# DUE_Xbee_v1.net
KiCad netlist of a schematic drawn in EAGLE
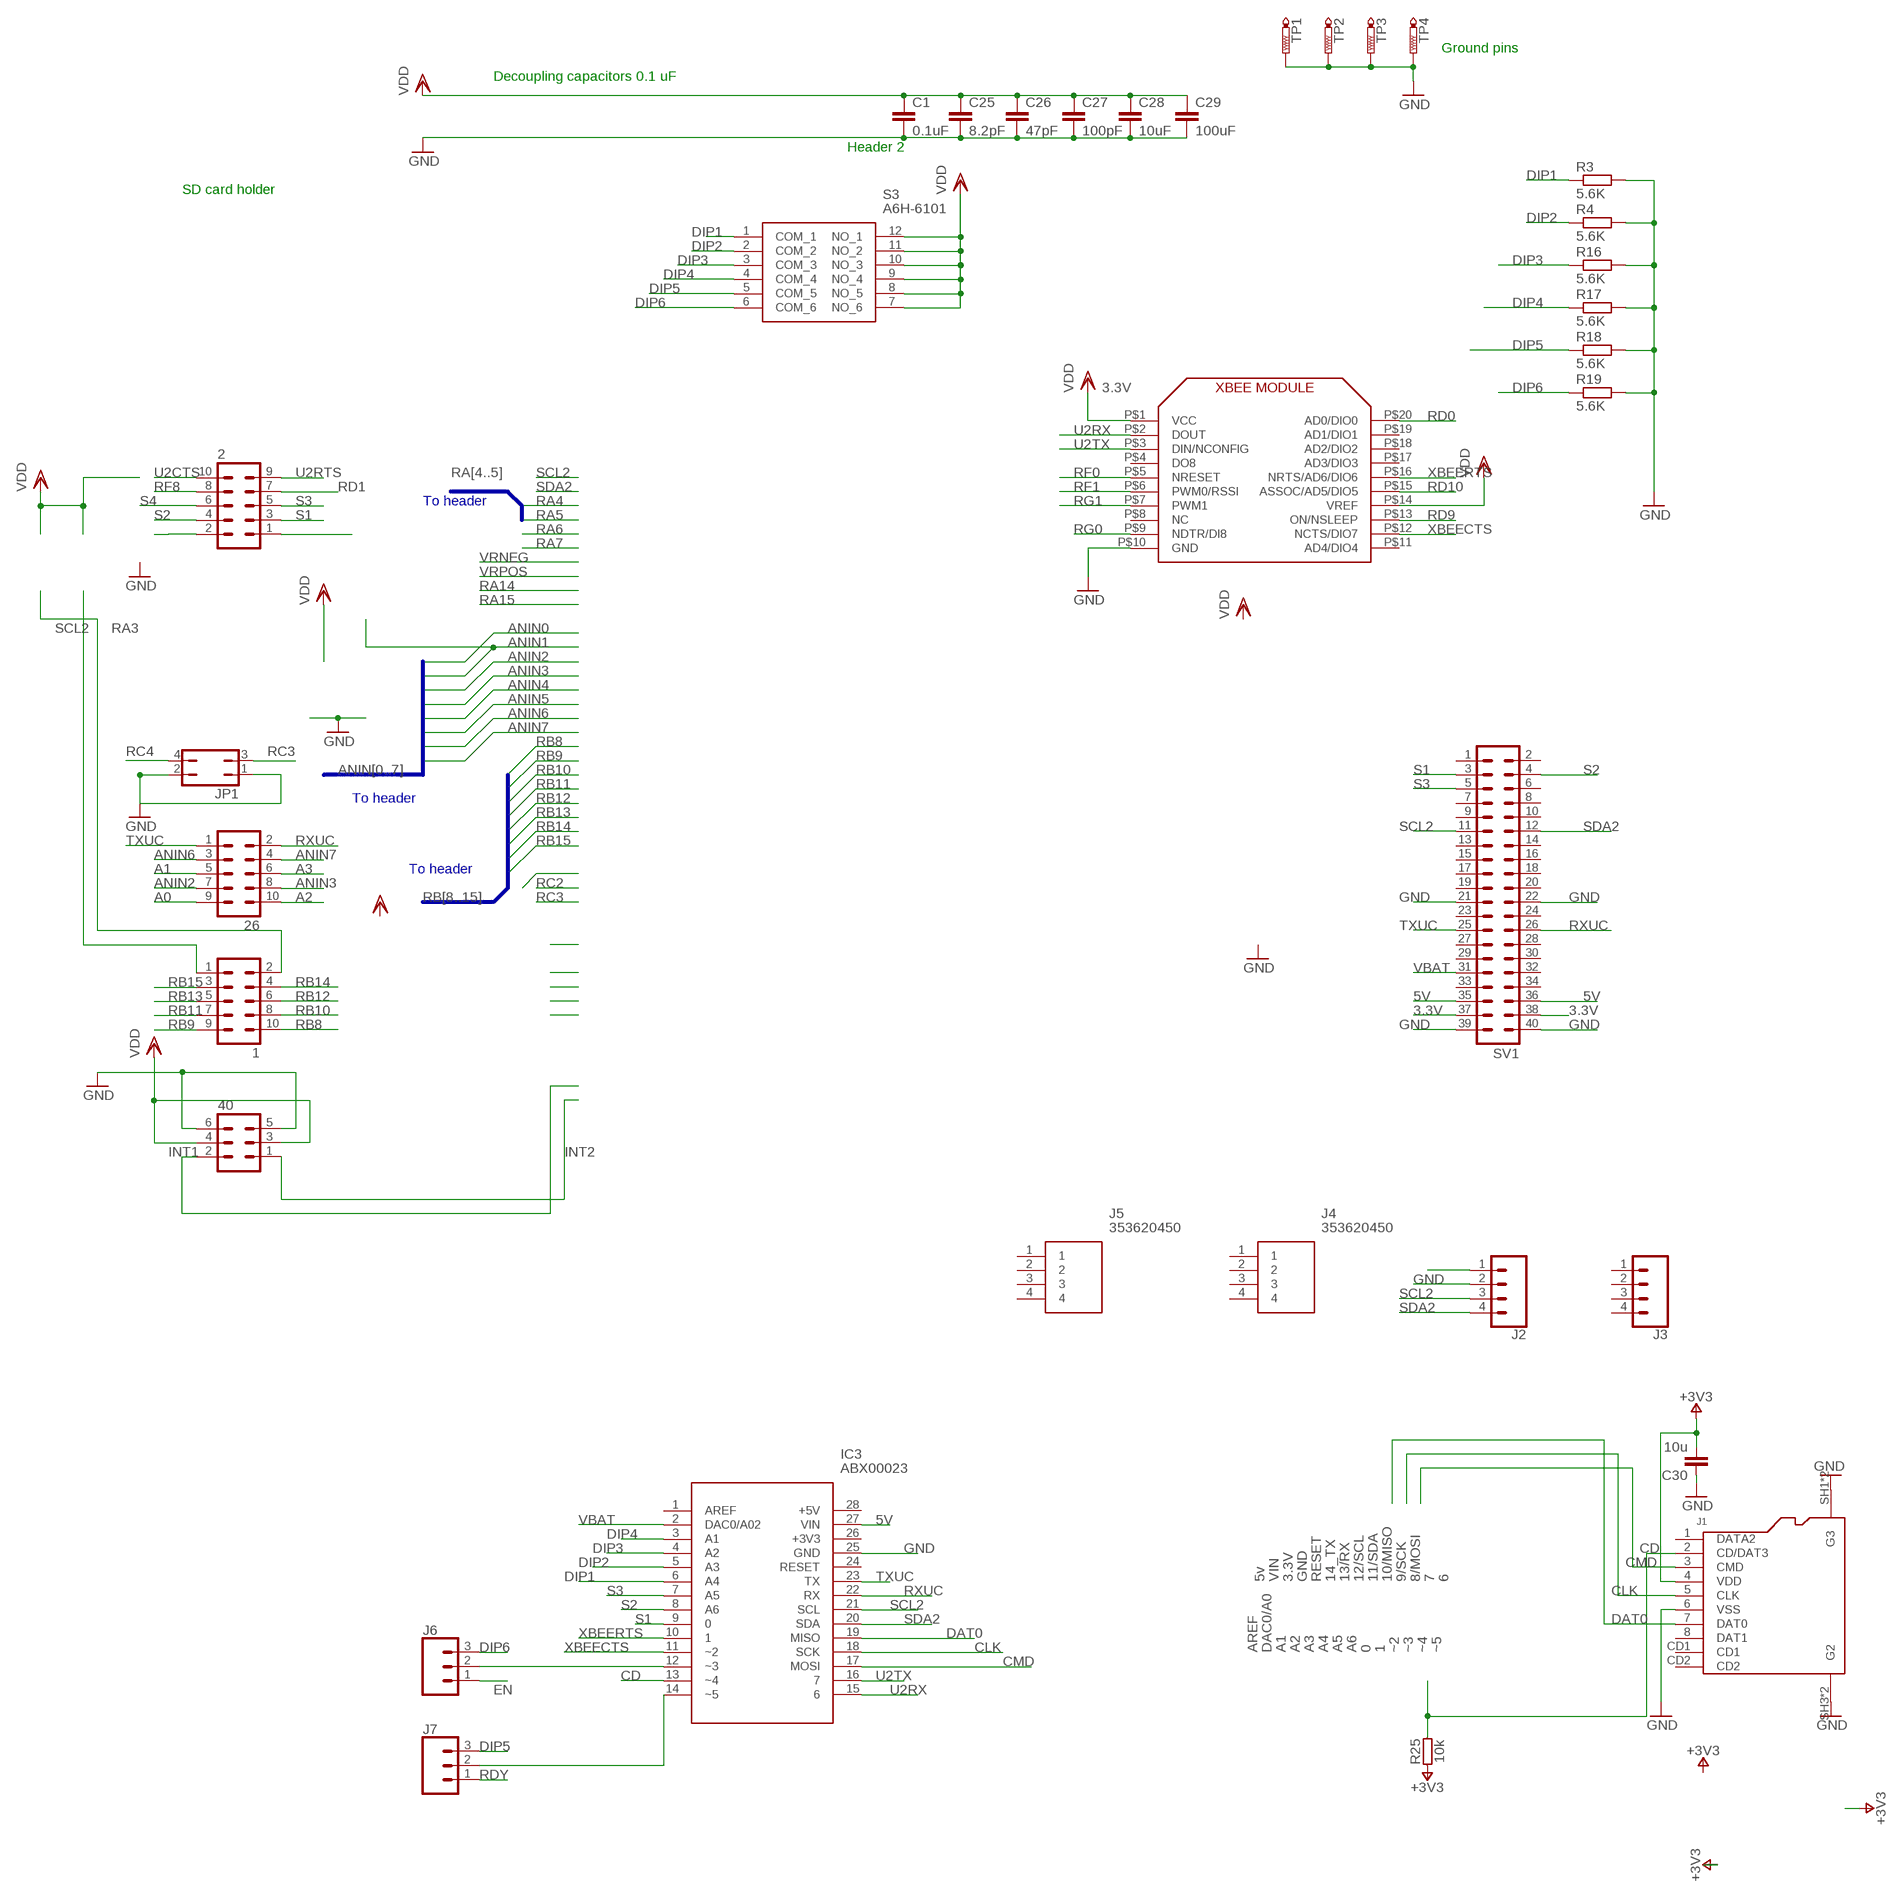
[diagram p0: schematic, sheet 1, part 1 of 2]
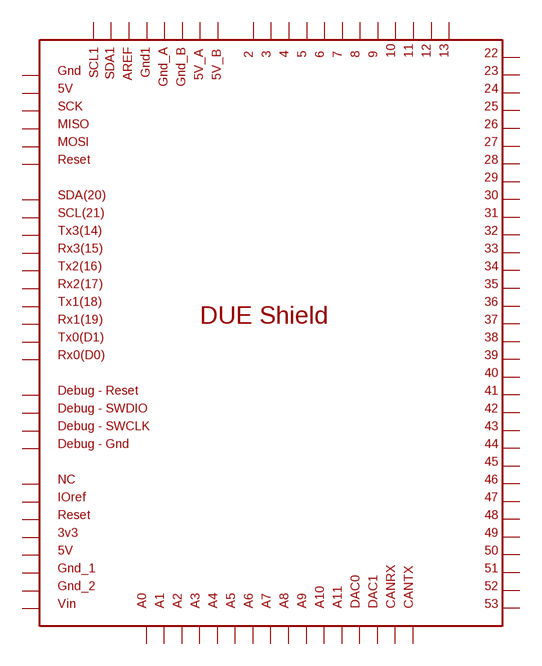
[diagram p1: schematic, sheet 1, part 2 of 2]

(export (version "E")
  (design (tool "Eeschema 10.0.6"))
  (components
    (comp (ref "1")
      (value "MA05-2")
      (footprint "eagle-import:MA05-2")
      (libsource (lib "eagle-import") (part "MA05-2"))
    )
    (comp (ref "2")
      (value "MA05-2")
      (footprint "eagle-import:MA05-2")
      (libsource (lib "eagle-import") (part "MA05-2"))
    )
    (comp (ref "26")
      (value "MA05-2")
      (footprint "eagle-import:MA05-2")
      (libsource (lib "eagle-import") (part "MA05-2"))
    )
    (comp (ref "40")
      (value "MA03-2")
      (footprint "eagle-import:MA03-2")
      (libsource (lib "eagle-import") (part "MA03-2"))
    )
    (comp (ref "C1")
      (value "0.1uF")
      (footprint "eagle-import:C0805K")
      (libsource (lib "eagle-import") (part "C-EUC0805K"))
    )
    (comp (ref "C25")
      (value "8.2pF")
      (footprint "eagle-import:C0805K")
      (libsource (lib "eagle-import") (part "C-EUC0805K"))
    )
    (comp (ref "C26")
      (value "47pF")
      (footprint "eagle-import:C0805K")
      (libsource (lib "eagle-import") (part "C-EUC0805K"))
    )
    (comp (ref "C27")
      (value "100pF")
      (footprint "eagle-import:C0805K")
      (libsource (lib "eagle-import") (part "C-EUC0805K"))
    )
    (comp (ref "C28")
      (value "10uF")
      (footprint "eagle-import:C0805K")
      (libsource (lib "eagle-import") (part "C-EUC0805K"))
    )
    (comp (ref "C29")
      (value "100uF")
      (footprint "eagle-import:C0805K")
      (libsource (lib "eagle-import") (part "C-EUC0805K"))
    )
    (comp (ref "C30")
      (value "10u")
      (footprint "eagle-import:0805-R2013X50N")
      (fields (field (name "MANUFACTURER") "Samsung"))
      (libsource (lib "eagle-import") (part "C-0805-22U"))
    )
    (comp (ref "IC3")
      (value "ABX00023")
      (footprint "eagle-import:ABX00023")
      (fields (field (name "MOUSER_PART_NUMBER") "782-ABX00023"))
      (libsource (lib "eagle-import") (part "ABX00023"))
    )
    (comp (ref "J1")
      (value "AMPHENOL_114-00841-68")
      (footprint "eagle-import:AMPHENOL_114-00841-68")
      (libsource (lib "eagle-import") (part "AMPHENOL_114-00841-68"))
    )
    (comp (ref "J2")
      (value "CONN_04POLAR_LOCK")
      (footprint "eagle-import:MOLEX-1X4_LOCK")
      (libsource (lib "eagle-import") (part "CONN_04POLAR_LOCK"))
    )
    (comp (ref "J3")
      (value "CONN_04POLAR_LOCK")
      (footprint "eagle-import:MOLEX-1X4_LOCK")
      (libsource (lib "eagle-import") (part "CONN_04POLAR_LOCK"))
    )
    (comp (ref "J4")
      (value "353620450")
      (footprint "eagle-import:SHDR4W50P0X200_1X4_1030X550X85")
      (libsource (lib "eagle-import") (part "353620450"))
    )
    (comp (ref "J5")
      (value "353620450")
      (footprint "eagle-import:SHDR4W50P0X200_1X4_1030X550X85")
      (libsource (lib "eagle-import") (part "353620450"))
    )
    (comp (ref "J6")
      (value "CONN_03LOCK")
      (footprint "eagle-import:1X03_LOCK")
      (libsource (lib "eagle-import") (part "CONN_03LOCK"))
    )
    (comp (ref "J7")
      (value "CONN_03LOCK")
      (footprint "eagle-import:1X03_LOCK")
      (libsource (lib "eagle-import") (part "CONN_03LOCK"))
    )
    (comp (ref "JP1")
      (value "JP2Q")
      (footprint "eagle-import:JP2Q")
      (libsource (lib "eagle-import") (part "JP2Q"))
    )
    (comp (ref "R3")
      (value "5.6K")
      (footprint "eagle-import:R0805")
      (libsource (lib "eagle-import") (part "R-EU_R0805"))
    )
    (comp (ref "R4")
      (value "5.6K")
      (footprint "eagle-import:R0805")
      (libsource (lib "eagle-import") (part "R-EU_R0805"))
    )
    (comp (ref "R16")
      (value "5.6K")
      (footprint "eagle-import:R0805")
      (libsource (lib "eagle-import") (part "R-EU_R0805"))
    )
    (comp (ref "R17")
      (value "5.6K")
      (footprint "eagle-import:R0805")
      (libsource (lib "eagle-import") (part "R-EU_R0805"))
    )
    (comp (ref "R18")
      (value "5.6K")
      (footprint "eagle-import:R0805")
      (libsource (lib "eagle-import") (part "R-EU_R0805"))
    )
    (comp (ref "R19")
      (value "5.6K")
      (footprint "eagle-import:R0805")
      (libsource (lib "eagle-import") (part "R-EU_R0805"))
    )
    (comp (ref "R25")
      (value "10k")
      (footprint "eagle-import:0805-R2013X50N")
      (fields (field (name "MANUFACTURER") "DNP"))
      (libsource (lib "eagle-import") (part "R-0805-DNP"))
    )
    (comp (ref "S3")
      (value "A6H-6101")
      (footprint "eagle-import:A6H6101")
      (fields (field (name "MOUSER_PART_NUMBER") "653-A6H-6101"))
      (libsource (lib "eagle-import") (part "A6H-6101"))
    )
    (comp (ref "SV1")
      (value "ML40")
      (footprint "eagle-import:ML40")
      (libsource (lib "eagle-import") (part "ML40"))
    )
    (comp (ref "TP1")
      (value "PTR1PAD1-13")
      (footprint "eagle-import:P1-13")
      (libsource (lib "eagle-import") (part "PTR1PAD1-13"))
    )
    (comp (ref "TP2")
      (value "PTR1PAD1-13")
      (footprint "eagle-import:P1-13")
      (libsource (lib "eagle-import") (part "PTR1PAD1-13"))
    )
    (comp (ref "TP3")
      (value "PTR1PAD1-13")
      (footprint "eagle-import:P1-13")
      (libsource (lib "eagle-import") (part "PTR1PAD1-13"))
    )
    (comp (ref "TP4")
      (value "PTR1PAD1-13")
      (footprint "eagle-import:P1-13")
      (libsource (lib "eagle-import") (part "PTR1PAD1-13"))
    )
    (comp (ref "U$1")
      (value "XBEE")
      (footprint "eagle-import:XBEE")
      (libsource (lib "eagle-import") (part "XBEE"))
    )
    (comp (ref "U$2")
      (value "DUE(NORMAL)")
      (footprint "eagle-import:DUE(NORMAL)")
      (libsource (lib "eagle-import") (part "DUE(NORMAL)"))
    )
  )
  (nets
    (net (code "1") (name "+3V3") (class "Default")
      (node (ref "C30") (pin "2") (pinfunction "2_2") (pintype "passive"))
      (node (ref "J1") (pin "4") (pinfunction "VDD_4") (pintype "power_in"))
      (node (ref "R25") (pin "1") (pinfunction "1_1") (pintype "passive"))
    )
    (net (code "2") (name "/5V") (class "Default")
      (node (ref "IC3") (pin "27") (pinfunction "VIN_27") (pintype "bidirectional"))
      (node (ref "SV1") (pin "35") (pinfunction "35_35") (pintype "passive"))
      (node (ref "SV1") (pin "36") (pinfunction "36_36") (pintype "passive"))
    )
    (net (code "3") (name "/A0") (class "Default")
      (node (ref "26") (pin "9") (pinfunction "9_9") (pintype "passive"))
    )
    (net (code "4") (name "/A1") (class "Default")
      (node (ref "26") (pin "5") (pinfunction "5_5") (pintype "passive"))
    )
    (net (code "5") (name "/A2") (class "Default")
      (node (ref "26") (pin "10") (pinfunction "10_10") (pintype "passive"))
    )
    (net (code "6") (name "/A3") (class "Default")
      (node (ref "26") (pin "6") (pinfunction "6_6") (pintype "passive"))
    )
    (net (code "9") (name "/ANIN2") (class "Default")
      (node (ref "26") (pin "7") (pinfunction "7_7") (pintype "passive"))
    )
    (net (code "10") (name "/ANIN3") (class "Default")
      (node (ref "26") (pin "8") (pinfunction "8_8") (pintype "passive"))
    )
    (net (code "13") (name "/ANIN6") (class "Default")
      (node (ref "26") (pin "3") (pinfunction "3_3") (pintype "passive"))
    )
    (net (code "14") (name "/ANIN7") (class "Default")
      (node (ref "26") (pin "4") (pinfunction "4_4") (pintype "passive"))
    )
    (net (code "16") (name "/CD") (class "Default")
      (node (ref "IC3") (pin "13") (pinfunction "~{4}_13") (pintype "bidirectional"))
      (node (ref "J1") (pin "2") (pinfunction "CD/DAT3_2") (pintype "bidirectional"))
      (node (ref "R25") (pin "2") (pinfunction "2_2") (pintype "passive"))
    )
    (net (code "17") (name "/CLK") (class "Default")
      (node (ref "IC3") (pin "18") (pinfunction "SCK_18") (pintype "bidirectional"))
      (node (ref "J1") (pin "5") (pinfunction "CLK_5") (pintype "bidirectional"))
    )
    (net (code "18") (name "/CMD") (class "Default")
      (node (ref "IC3") (pin "17") (pinfunction "MOSI_17") (pintype "bidirectional"))
      (node (ref "J1") (pin "3") (pinfunction "CMD_3") (pintype "bidirectional"))
    )
    (net (code "19") (name "/DAT0") (class "Default")
      (node (ref "IC3") (pin "19") (pinfunction "MISO_19") (pintype "bidirectional"))
      (node (ref "J1") (pin "7") (pinfunction "DAT0_7") (pintype "bidirectional"))
    )
    (net (code "20") (name "/DIP1") (class "Default")
      (node (ref "IC3") (pin "6") (pinfunction "A4_6") (pintype "bidirectional"))
      (node (ref "R3") (pin "1") (pinfunction "1_1") (pintype "passive"))
      (node (ref "S3") (pin "1") (pinfunction "COM_1_1") (pintype "bidirectional"))
    )
    (net (code "21") (name "/DIP2") (class "Default")
      (node (ref "IC3") (pin "5") (pinfunction "A3_5") (pintype "bidirectional"))
      (node (ref "R4") (pin "1") (pinfunction "1_1") (pintype "passive"))
      (node (ref "S3") (pin "2") (pinfunction "COM_2_2") (pintype "bidirectional"))
    )
    (net (code "22") (name "/DIP3") (class "Default")
      (node (ref "IC3") (pin "4") (pinfunction "A2_4") (pintype "bidirectional"))
      (node (ref "R16") (pin "1") (pinfunction "1_1") (pintype "passive"))
      (node (ref "S3") (pin "3") (pinfunction "COM_3_3") (pintype "bidirectional"))
    )
    (net (code "23") (name "/DIP4") (class "Default")
      (node (ref "IC3") (pin "3") (pinfunction "A1_3") (pintype "bidirectional"))
      (node (ref "R17") (pin "1") (pinfunction "1_1") (pintype "passive"))
      (node (ref "S3") (pin "4") (pinfunction "COM_4_4") (pintype "bidirectional"))
    )
    (net (code "24") (name "/DIP5") (class "Default")
      (node (ref "J7") (pin "3") (pinfunction "3_3") (pintype "passive"))
      (node (ref "R18") (pin "1") (pinfunction "1_1") (pintype "passive"))
      (node (ref "S3") (pin "5") (pinfunction "COM_5_5") (pintype "bidirectional"))
    )
    (net (code "25") (name "/DIP6") (class "Default")
      (node (ref "J6") (pin "3") (pinfunction "3_3") (pintype "passive"))
      (node (ref "R19") (pin "1") (pinfunction "1_1") (pintype "passive"))
      (node (ref "S3") (pin "6") (pinfunction "COM_6_6") (pintype "bidirectional"))
    )
    (net (code "26") (name "/EN") (class "Default")
      (node (ref "J6") (pin "1") (pinfunction "1_1") (pintype "passive"))
    )
    (net (code "27") (name "/INT1") (class "Default")
      (node (ref "40") (pin "2") (pinfunction "2_2") (pintype "passive"))
    )
    (net (code "28") (name "/INT2") (class "Default")
      (node (ref "40") (pin "1") (pinfunction "1_1") (pintype "passive"))
    )
    (net (code "29") (name "/RA3") (class "Default")
      (node (ref "1") (pin "2") (pinfunction "2_2") (pintype "passive"))
    )
    (net (code "30") (name "/RA4") (class "Default")
      (node (ref "IC3") (pin "20") (pinfunction "SDA_20") (pintype "bidirectional"))
      (node (ref "J2") (pin "4") (pinfunction "4_4") (pintype "passive"))
      (node (ref "SV1") (pin "12") (pinfunction "12_12") (pintype "passive"))
    )
    (net (code "37") (name "/RB8") (class "Default")
      (node (ref "1") (pin "10") (pinfunction "10_10") (pintype "passive"))
    )
    (net (code "38") (name "/RB9") (class "Default")
      (node (ref "1") (pin "9") (pinfunction "9_9") (pintype "passive"))
    )
    (net (code "39") (name "/RB10") (class "Default")
      (node (ref "1") (pin "8") (pinfunction "8_8") (pintype "passive"))
    )
    (net (code "40") (name "/RB11") (class "Default")
      (node (ref "1") (pin "7") (pinfunction "7_7") (pintype "passive"))
    )
    (net (code "41") (name "/RB12") (class "Default")
      (node (ref "1") (pin "6") (pinfunction "6_6") (pintype "passive"))
    )
    (net (code "42") (name "/RB13") (class "Default")
      (node (ref "1") (pin "5") (pinfunction "5_5") (pintype "passive"))
    )
    (net (code "43") (name "/RB14") (class "Default")
      (node (ref "1") (pin "4") (pinfunction "4_4") (pintype "passive"))
    )
    (net (code "44") (name "/RB15") (class "Default")
      (node (ref "1") (pin "3") (pinfunction "3_3") (pintype "passive"))
    )
    (net (code "47") (name "/RC3") (class "Default")
      (node (ref "JP1") (pin "3") (pinfunction "3_3") (pintype "passive"))
    )
    (net (code "48") (name "/RC4") (class "Default")
      (node (ref "JP1") (pin "4") (pinfunction "4_4") (pintype "passive"))
    )
    (net (code "49") (name "/RD0") (class "Default")
      (node (ref "U$1") (pin "P$20") (pinfunction "AD0/DIO0_P$20") (pintype "bidirectional"))
    )
    (net (code "50") (name "/RD1") (class "Default")
      (node (ref "2") (pin "7") (pinfunction "7_7") (pintype "passive"))
    )
    (net (code "51") (name "/RD9") (class "Default")
      (node (ref "U$1") (pin "P$13") (pinfunction "ON/NSLEEP_P$13") (pintype "bidirectional"))
    )
    (net (code "52") (name "/RD10") (class "Default")
      (node (ref "U$1") (pin "P$15") (pinfunction "ASSOC/AD5/DIO5_P$15") (pintype "bidirectional"))
    )
    (net (code "53") (name "/RDY") (class "Default")
      (node (ref "J7") (pin "1") (pinfunction "1_1") (pintype "passive"))
    )
    (net (code "54") (name "/RF0") (class "Default")
      (node (ref "U$1") (pin "P$5") (pinfunction "NRESET_P$5") (pintype "bidirectional"))
    )
    (net (code "55") (name "/RF1") (class "Default")
      (node (ref "U$1") (pin "P$6") (pinfunction "PWM0/RSSI_P$6") (pintype "bidirectional"))
    )
    (net (code "56") (name "/RF8") (class "Default")
      (node (ref "2") (pin "8") (pinfunction "8_8") (pintype "passive"))
    )
    (net (code "57") (name "/RG0") (class "Default")
      (node (ref "U$1") (pin "P$9") (pinfunction "NDTR/DI8_P$9") (pintype "bidirectional"))
    )
    (net (code "58") (name "/RG1") (class "Default")
      (node (ref "U$1") (pin "P$7") (pinfunction "PWM1_P$7") (pintype "bidirectional"))
    )
    (net (code "59") (name "/RXUC") (class "Default")
      (node (ref "26") (pin "2") (pinfunction "2_2") (pintype "passive"))
      (node (ref "IC3") (pin "22") (pinfunction "RX_22") (pintype "bidirectional"))
      (node (ref "SV1") (pin "26") (pinfunction "26_26") (pintype "passive"))
    )
    (net (code "60") (name "/S1") (class "Default")
      (node (ref "2") (pin "3") (pinfunction "3_3") (pintype "passive"))
      (node (ref "IC3") (pin "9") (pinfunction "0_9") (pintype "bidirectional"))
      (node (ref "SV1") (pin "3") (pinfunction "3_3") (pintype "passive"))
    )
    (net (code "61") (name "/S2") (class "Default")
      (node (ref "2") (pin "4") (pinfunction "4_4") (pintype "passive"))
      (node (ref "IC3") (pin "8") (pinfunction "A6_8") (pintype "bidirectional"))
      (node (ref "SV1") (pin "4") (pinfunction "4_4") (pintype "passive"))
    )
    (net (code "62") (name "/S3") (class "Default")
      (node (ref "2") (pin "5") (pinfunction "5_5") (pintype "passive"))
      (node (ref "IC3") (pin "7") (pinfunction "A5_7") (pintype "bidirectional"))
      (node (ref "SV1") (pin "5") (pinfunction "5_5") (pintype "passive"))
    )
    (net (code "63") (name "/S4") (class "Default")
      (node (ref "2") (pin "6") (pinfunction "6_6") (pintype "passive"))
    )
    (net (code "64") (name "/SCL2") (class "Default")
      (node (ref "1") (pin "1") (pinfunction "1_1") (pintype "passive"))
      (node (ref "IC3") (pin "21") (pinfunction "SCL_21") (pintype "bidirectional"))
      (node (ref "J2") (pin "3") (pinfunction "3_3") (pintype "passive"))
      (node (ref "SV1") (pin "11") (pinfunction "11_11") (pintype "passive"))
    )
    (net (code "65") (name "/TXUC") (class "Default")
      (node (ref "26") (pin "1") (pinfunction "1_1") (pintype "passive"))
      (node (ref "IC3") (pin "23") (pinfunction "TX_23") (pintype "bidirectional"))
      (node (ref "SV1") (pin "25") (pinfunction "25_25") (pintype "passive"))
    )
    (net (code "66") (name "/U2CTS") (class "Default")
      (node (ref "2") (pin "10") (pinfunction "10_10") (pintype "passive"))
    )
    (net (code "67") (name "/U2RTS") (class "Default")
      (node (ref "2") (pin "9") (pinfunction "9_9") (pintype "passive"))
    )
    (net (code "68") (name "/U2RX") (class "Default")
      (node (ref "IC3") (pin "15") (pinfunction "6_15") (pintype "bidirectional"))
      (node (ref "U$1") (pin "P$2") (pinfunction "DOUT_P$2") (pintype "bidirectional"))
    )
    (net (code "69") (name "/U2TX") (class "Default")
      (node (ref "IC3") (pin "16") (pinfunction "7_16") (pintype "bidirectional"))
      (node (ref "U$1") (pin "P$3") (pinfunction "DIN/NCONFIG_P$3") (pintype "bidirectional"))
    )
    (net (code "70") (name "/VBAT") (class "Default")
      (node (ref "IC3") (pin "2") (pinfunction "DAC0/A02_2") (pintype "bidirectional"))
      (node (ref "SV1") (pin "31") (pinfunction "31_31") (pintype "passive"))
    )
    (net (code "73") (name "/XBEECTS") (class "Default")
      (node (ref "IC3") (pin "11") (pinfunction "~{2}_11") (pintype "bidirectional"))
      (node (ref "U$1") (pin "P$12") (pinfunction "NCTS/DIO7_P$12") (pintype "bidirectional"))
    )
    (net (code "74") (name "/XBEERTS") (class "Default")
      (node (ref "IC3") (pin "10") (pinfunction "1_10") (pintype "bidirectional"))
      (node (ref "U$1") (pin "P$16") (pinfunction "NRTS/AD6/DIO6_P$16") (pintype "bidirectional"))
    )
    (net (code "75") (name "GND") (class "Default")
      (node (ref "40") (pin "5") (pinfunction "5_5") (pintype "passive"))
      (node (ref "40") (pin "6") (pinfunction "6_6") (pintype "passive"))
      (node (ref "C1") (pin "2") (pinfunction "2_2") (pintype "passive"))
      (node (ref "C25") (pin "2") (pinfunction "2_2") (pintype "passive"))
      (node (ref "C26") (pin "2") (pinfunction "2_2") (pintype "passive"))
      (node (ref "C27") (pin "2") (pinfunction "2_2") (pintype "passive"))
      (node (ref "C28") (pin "2") (pinfunction "2_2") (pintype "passive"))
      (node (ref "C29") (pin "2") (pinfunction "2_2") (pintype "passive"))
      (node (ref "C30") (pin "1") (pinfunction "1_1") (pintype "passive"))
      (node (ref "IC3") (pin "25") (pinfunction "GND_25") (pintype "bidirectional"))
      (node (ref "J1") (pin "6") (pinfunction "VSS_6") (pintype "power_in"))
      (node (ref "J1") (pin "SH1") (pinfunction "G3_SH1") (pintype "bidirectional"))
      (node (ref "J1") (pin "SH2") (pinfunction "G3_SH2") (pintype "bidirectional"))
      (node (ref "J1") (pin "SH3") (pinfunction "G2_SH3") (pintype "bidirectional"))
      (node (ref "J1") (pin "SH4") (pinfunction "G2_SH4") (pintype "bidirectional"))
      (node (ref "J2") (pin "2") (pinfunction "2_2") (pintype "passive"))
      (node (ref "JP1") (pin "1") (pinfunction "1_1") (pintype "passive"))
      (node (ref "JP1") (pin "2") (pinfunction "2_2") (pintype "passive"))
      (node (ref "R16") (pin "2") (pinfunction "2_2") (pintype "passive"))
      (node (ref "R17") (pin "2") (pinfunction "2_2") (pintype "passive"))
      (node (ref "R18") (pin "2") (pinfunction "2_2") (pintype "passive"))
      (node (ref "R19") (pin "2") (pinfunction "2_2") (pintype "passive"))
      (node (ref "R3") (pin "2") (pinfunction "2_2") (pintype "passive"))
      (node (ref "R4") (pin "2") (pinfunction "2_2") (pintype "passive"))
      (node (ref "SV1") (pin "21") (pinfunction "21_21") (pintype "passive"))
      (node (ref "SV1") (pin "22") (pinfunction "22_22") (pintype "passive"))
      (node (ref "SV1") (pin "39") (pinfunction "39_39") (pintype "passive"))
      (node (ref "SV1") (pin "40") (pinfunction "40_40") (pintype "passive"))
      (node (ref "TP1") (pin "1") (pinfunction "TP_1") (pintype "input"))
      (node (ref "TP2") (pin "1") (pinfunction "TP_1") (pintype "input"))
      (node (ref "TP3") (pin "1") (pinfunction "TP_1") (pintype "input"))
      (node (ref "TP4") (pin "1") (pinfunction "TP_1") (pintype "input"))
      (node (ref "U$1") (pin "P$10") (pinfunction "GND_P$10") (pintype "bidirectional"))
    )
    (net (code "76") (name "Net-(IC3-~{3})") (class "Default")
      (node (ref "IC3") (pin "12") (pinfunction "~{3}_12") (pintype "bidirectional"))
      (node (ref "J6") (pin "2") (pinfunction "2_2") (pintype "passive"))
    )
    (net (code "77") (name "Net-(IC3-~{5})") (class "Default")
      (node (ref "IC3") (pin "14") (pinfunction "~{5}_14") (pintype "bidirectional"))
      (node (ref "J7") (pin "2") (pinfunction "2_2") (pintype "passive"))
    )
    (net (code "78") (name "VDD") (class "Default")
      (node (ref "40") (pin "3") (pinfunction "3_3") (pintype "passive"))
      (node (ref "40") (pin "4") (pinfunction "4_4") (pintype "passive"))
      (node (ref "C1") (pin "1") (pinfunction "1_1") (pintype "passive"))
      (node (ref "C25") (pin "1") (pinfunction "1_1") (pintype "passive"))
      (node (ref "C26") (pin "1") (pinfunction "1_1") (pintype "passive"))
      (node (ref "C27") (pin "1") (pinfunction "1_1") (pintype "passive"))
      (node (ref "C28") (pin "1") (pinfunction "1_1") (pintype "passive"))
      (node (ref "C29") (pin "1") (pinfunction "1_1") (pintype "passive"))
      (node (ref "J2") (pin "1") (pinfunction "1_1") (pintype "passive"))
      (node (ref "S3") (pin "10") (pinfunction "NO_3_10") (pintype "bidirectional"))
      (node (ref "S3") (pin "11") (pinfunction "NO_2_11") (pintype "bidirectional"))
      (node (ref "S3") (pin "12") (pinfunction "NO_1_12") (pintype "bidirectional"))
      (node (ref "S3") (pin "7") (pinfunction "NO_6_7") (pintype "bidirectional"))
      (node (ref "S3") (pin "8") (pinfunction "NO_5_8") (pintype "bidirectional"))
      (node (ref "S3") (pin "9") (pinfunction "NO_4_9") (pintype "bidirectional"))
      (node (ref "SV1") (pin "37") (pinfunction "37_37") (pintype "passive"))
      (node (ref "SV1") (pin "38") (pinfunction "38_38") (pintype "passive"))
      (node (ref "U$1") (pin "P$1") (pinfunction "VCC_P$1") (pintype "bidirectional"))
      (node (ref "U$1") (pin "P$14") (pinfunction "VREF_P$14") (pintype "bidirectional"))
    )
    (net (code "79") (name "unconnected-(2-Pad1)") (class "Default")
      (node (ref "2") (pin "1") (pinfunction "1_1") (pintype "passive"))
    )
    (net (code "80") (name "unconnected-(2-Pad2)") (class "Default")
      (node (ref "2") (pin "2") (pinfunction "2_2") (pintype "passive"))
    )
    (net (code "81") (name "unconnected-(IC3-+3V3-Pad26)") (class "Default")
      (node (ref "IC3") (pin "26") (pinfunction "+3V3_26") (pintype "bidirectional"))
    )
    (net (code "82") (name "unconnected-(IC3-+5V-Pad28)") (class "Default")
      (node (ref "IC3") (pin "28") (pinfunction "+5V_28") (pintype "bidirectional"))
    )
    (net (code "83") (name "unconnected-(IC3-AREF-Pad1)") (class "Default")
      (node (ref "IC3") (pin "1") (pinfunction "AREF_1") (pintype "bidirectional"))
    )
    (net (code "84") (name "unconnected-(IC3-RESET-Pad24)") (class "Default")
      (node (ref "IC3") (pin "24") (pinfunction "RESET_24") (pintype "bidirectional"))
    )
    (net (code "85") (name "unconnected-(J1-DAT1-Pad8)") (class "Default")
      (node (ref "J1") (pin "8") (pinfunction "DAT1_8") (pintype "bidirectional"))
    )
    (net (code "86") (name "unconnected-(J1-DATA2-Pad1)") (class "Default")
      (node (ref "J1") (pin "1") (pinfunction "DATA2_1") (pintype "bidirectional"))
    )
    (net (code "87") (name "unconnected-(J1-PadCD1)") (class "Default")
      (node (ref "J1") (pin "CD1") (pinfunction "CD1_CD1") (pintype "bidirectional"))
    )
    (net (code "88") (name "unconnected-(J1-PadCD2)") (class "Default")
      (node (ref "J1") (pin "CD2") (pinfunction "CD2_CD2") (pintype "bidirectional"))
    )
    (net (code "89") (name "unconnected-(J3-Pad1)") (class "Default")
      (node (ref "J3") (pin "1") (pinfunction "1_1") (pintype "passive"))
    )
    (net (code "90") (name "unconnected-(J3-Pad2)") (class "Default")
      (node (ref "J3") (pin "2") (pinfunction "2_2") (pintype "passive"))
    )
    (net (code "91") (name "unconnected-(J3-Pad3)") (class "Default")
      (node (ref "J3") (pin "3") (pinfunction "3_3") (pintype "passive"))
    )
    (net (code "92") (name "unconnected-(J3-Pad4)") (class "Default")
      (node (ref "J3") (pin "4") (pinfunction "4_4") (pintype "passive"))
    )
    (net (code "93") (name "unconnected-(J4-Pad1)") (class "Default")
      (node (ref "J4") (pin "1") (pinfunction "1_1") (pintype "bidirectional"))
    )
    (net (code "94") (name "unconnected-(J4-Pad2)") (class "Default")
      (node (ref "J4") (pin "2") (pinfunction "2_2") (pintype "bidirectional"))
    )
    (net (code "95") (name "unconnected-(J4-Pad3)") (class "Default")
      (node (ref "J4") (pin "3") (pinfunction "3_3") (pintype "bidirectional"))
    )
    (net (code "96") (name "unconnected-(J4-Pad4)") (class "Default")
      (node (ref "J4") (pin "4") (pinfunction "4_4") (pintype "bidirectional"))
    )
    (net (code "97") (name "unconnected-(J5-Pad1)") (class "Default")
      (node (ref "J5") (pin "1") (pinfunction "1_1") (pintype "bidirectional"))
    )
    (net (code "98") (name "unconnected-(J5-Pad2)") (class "Default")
      (node (ref "J5") (pin "2") (pinfunction "2_2") (pintype "bidirectional"))
    )
    (net (code "99") (name "unconnected-(J5-Pad3)") (class "Default")
      (node (ref "J5") (pin "3") (pinfunction "3_3") (pintype "bidirectional"))
    )
    (net (code "100") (name "unconnected-(J5-Pad4)") (class "Default")
      (node (ref "J5") (pin "4") (pinfunction "4_4") (pintype "bidirectional"))
    )
    (net (code "101") (name "unconnected-(SV1-Pad1)") (class "Default")
      (node (ref "SV1") (pin "1") (pinfunction "1_1") (pintype "passive"))
    )
    (net (code "102") (name "unconnected-(SV1-Pad2)") (class "Default")
      (node (ref "SV1") (pin "2") (pinfunction "2_2") (pintype "passive"))
    )
    (net (code "103") (name "unconnected-(SV1-Pad6)") (class "Default")
      (node (ref "SV1") (pin "6") (pinfunction "6_6") (pintype "passive"))
    )
    (net (code "104") (name "unconnected-(SV1-Pad7)") (class "Default")
      (node (ref "SV1") (pin "7") (pinfunction "7_7") (pintype "passive"))
    )
    (net (code "105") (name "unconnected-(SV1-Pad8)") (class "Default")
      (node (ref "SV1") (pin "8") (pinfunction "8_8") (pintype "passive"))
    )
    (net (code "106") (name "unconnected-(SV1-Pad9)") (class "Default")
      (node (ref "SV1") (pin "9") (pinfunction "9_9") (pintype "passive"))
    )
    (net (code "107") (name "unconnected-(SV1-Pad10)") (class "Default")
      (node (ref "SV1") (pin "10") (pinfunction "10_10") (pintype "passive"))
    )
    (net (code "108") (name "unconnected-(SV1-Pad13)") (class "Default")
      (node (ref "SV1") (pin "13") (pinfunction "13_13") (pintype "passive"))
    )
    (net (code "109") (name "unconnected-(SV1-Pad14)") (class "Default")
      (node (ref "SV1") (pin "14") (pinfunction "14_14") (pintype "passive"))
    )
    (net (code "110") (name "unconnected-(SV1-Pad15)") (class "Default")
      (node (ref "SV1") (pin "15") (pinfunction "15_15") (pintype "passive"))
    )
    (net (code "111") (name "unconnected-(SV1-Pad16)") (class "Default")
      (node (ref "SV1") (pin "16") (pinfunction "16_16") (pintype "passive"))
    )
    (net (code "112") (name "unconnected-(SV1-Pad17)") (class "Default")
      (node (ref "SV1") (pin "17") (pinfunction "17_17") (pintype "passive"))
    )
    (net (code "113") (name "unconnected-(SV1-Pad18)") (class "Default")
      (node (ref "SV1") (pin "18") (pinfunction "18_18") (pintype "passive"))
    )
    (net (code "114") (name "unconnected-(SV1-Pad19)") (class "Default")
      (node (ref "SV1") (pin "19") (pinfunction "19_19") (pintype "passive"))
    )
    (net (code "115") (name "unconnected-(SV1-Pad20)") (class "Default")
      (node (ref "SV1") (pin "20") (pinfunction "20_20") (pintype "passive"))
    )
    (net (code "116") (name "unconnected-(SV1-Pad23)") (class "Default")
      (node (ref "SV1") (pin "23") (pinfunction "23_23") (pintype "passive"))
    )
    (net (code "117") (name "unconnected-(SV1-Pad24)") (class "Default")
      (node (ref "SV1") (pin "24") (pinfunction "24_24") (pintype "passive"))
    )
    (net (code "118") (name "unconnected-(SV1-Pad27)") (class "Default")
      (node (ref "SV1") (pin "27") (pinfunction "27_27") (pintype "passive"))
    )
    (net (code "119") (name "unconnected-(SV1-Pad28)") (class "Default")
      (node (ref "SV1") (pin "28") (pinfunction "28_28") (pintype "passive"))
    )
    (net (code "120") (name "unconnected-(SV1-Pad29)") (class "Default")
      (node (ref "SV1") (pin "29") (pinfunction "29_29") (pintype "passive"))
    )
    (net (code "121") (name "unconnected-(SV1-Pad30)") (class "Default")
      (node (ref "SV1") (pin "30") (pinfunction "30_30") (pintype "passive"))
    )
    (net (code "122") (name "unconnected-(SV1-Pad32)") (class "Default")
      (node (ref "SV1") (pin "32") (pinfunction "32_32") (pintype "passive"))
    )
    (net (code "123") (name "unconnected-(SV1-Pad33)") (class "Default")
      (node (ref "SV1") (pin "33") (pinfunction "33_33") (pintype "passive"))
    )
    (net (code "124") (name "unconnected-(SV1-Pad34)") (class "Default")
      (node (ref "SV1") (pin "34") (pinfunction "34_34") (pintype "passive"))
    )
    (net (code "125") (name "unconnected-(U$1-AD1{slash}DIO1-PadP$19)") (class "Default")
      (node (ref "U$1") (pin "P$19") (pinfunction "AD1/DIO1_P$19") (pintype "bidirectional"))
    )
    (net (code "126") (name "unconnected-(U$1-AD2{slash}DIO2-PadP$18)") (class "Default")
      (node (ref "U$1") (pin "P$18") (pinfunction "AD2/DIO2_P$18") (pintype "bidirectional"))
    )
    (net (code "127") (name "unconnected-(U$1-AD3{slash}DIO3-PadP$17)") (class "Default")
      (node (ref "U$1") (pin "P$17") (pinfunction "AD3/DIO3_P$17") (pintype "bidirectional"))
    )
    (net (code "128") (name "unconnected-(U$1-AD4{slash}DIO4-PadP$11)") (class "Default")
      (node (ref "U$1") (pin "P$11") (pinfunction "AD4/DIO4_P$11") (pintype "bidirectional"))
    )
    (net (code "129") (name "unconnected-(U$1-DO8-PadP$4)") (class "Default")
      (node (ref "U$1") (pin "P$4") (pinfunction "DO8_P$4") (pintype "bidirectional"))
    )
    (net (code "130") (name "unconnected-(U$1-NC-PadP$8)") (class "Default")
      (node (ref "U$1") (pin "P$8") (pinfunction "NC_P$8") (pintype "bidirectional"))
    )
    (net (code "131") (name "unconnected-(U$2-Pad2)") (class "Default")
      (node (ref "U$2") (pin "2") (pinfunction "2_2") (pintype "bidirectional"))
    )
    (net (code "132") (name "unconnected-(U$2-Pad3)") (class "Default")
      (node (ref "U$2") (pin "3") (pinfunction "3_3") (pintype "bidirectional"))
    )
    (net (code "133") (name "unconnected-(U$2-Pad3V3)") (class "Default")
      (node (ref "U$2") (pin "3V3") (pinfunction "3V3_3V3") (pintype "bidirectional"))
    )
    (net (code "134") (name "unconnected-(U$2-Pad4)") (class "Default")
      (node (ref "U$2") (pin "4") (pinfunction "4_4") (pintype "bidirectional"))
    )
    (net (code "135") (name "unconnected-(U$2-Pad5)") (class "Default")
      (node (ref "U$2") (pin "5") (pinfunction "5_5") (pintype "bidirectional"))
    )
    (net (code "136") (name "unconnected-(U$2-Pad5V)") (class "Default")
      (node (ref "U$2") (pin "5V") (pinfunction "5V_5V") (pintype "bidirectional"))
    )
    (net (code "137") (name "unconnected-(U$2-Pad5V_A)") (class "Default")
      (node (ref "U$2") (pin "5V_A") (pinfunction "5V_A_5V_A") (pintype "bidirectional"))
    )
    (net (code "138") (name "unconnected-(U$2-Pad5V_B)") (class "Default")
      (node (ref "U$2") (pin "5V_B") (pinfunction "5V_B_5V_B") (pintype "bidirectional"))
    )
    (net (code "139") (name "unconnected-(U$2-Pad5V_ICSP)") (class "Default")
      (node (ref "U$2") (pin "5V_ICSP") (pinfunction "5V_ICSP_5V_ICSP") (pintype "bidirectional"))
    )
    (net (code "140") (name "unconnected-(U$2-Pad6)") (class "Default")
      (node (ref "U$2") (pin "6") (pinfunction "6_6") (pintype "bidirectional"))
    )
    (net (code "141") (name "unconnected-(U$2-Pad7)") (class "Default")
      (node (ref "U$2") (pin "7") (pinfunction "7_7") (pintype "bidirectional"))
    )
    (net (code "142") (name "unconnected-(U$2-Pad8)") (class "Default")
      (node (ref "U$2") (pin "8") (pinfunction "8_8") (pintype "bidirectional"))
    )
    (net (code "143") (name "unconnected-(U$2-Pad9)") (class "Default")
      (node (ref "U$2") (pin "9") (pinfunction "9_9") (pintype "bidirectional"))
    )
    (net (code "144") (name "unconnected-(U$2-Pad10)") (class "Default")
      (node (ref "U$2") (pin "10") (pinfunction "10_10") (pintype "bidirectional"))
    )
    (net (code "145") (name "unconnected-(U$2-Pad11)") (class "Default")
      (node (ref "U$2") (pin "11") (pinfunction "11_11") (pintype "bidirectional"))
    )
    (net (code "146") (name "unconnected-(U$2-Pad12)") (class "Default")
      (node (ref "U$2") (pin "12") (pinfunction "12_12") (pintype "bidirectional"))
    )
    (net (code "147") (name "unconnected-(U$2-Pad13)") (class "Default")
      (node (ref "U$2") (pin "13") (pinfunction "13_13") (pintype "bidirectional"))
    )
    (net (code "148") (name "unconnected-(U$2-Pad22)") (class "Default")
      (node (ref "U$2") (pin "22") (pinfunction "22_22") (pintype "bidirectional"))
    )
    (net (code "149") (name "unconnected-(U$2-Pad23)") (class "Default")
      (node (ref "U$2") (pin "23") (pinfunction "23_23") (pintype "bidirectional"))
    )
    (net (code "150") (name "unconnected-(U$2-Pad24)") (class "Default")
      (node (ref "U$2") (pin "24") (pinfunction "24_24") (pintype "bidirectional"))
    )
    (net (code "151") (name "unconnected-(U$2-Pad25)") (class "Default")
      (node (ref "U$2") (pin "25") (pinfunction "25_25") (pintype "bidirectional"))
    )
    (net (code "152") (name "unconnected-(U$2-Pad26)") (class "Default")
      (node (ref "U$2") (pin "26") (pinfunction "26_26") (pintype "bidirectional"))
    )
    (net (code "153") (name "unconnected-(U$2-Pad27)") (class "Default")
      (node (ref "U$2") (pin "27") (pinfunction "27_27") (pintype "bidirectional"))
    )
    (net (code "154") (name "unconnected-(U$2-Pad28)") (class "Default")
      (node (ref "U$2") (pin "28") (pinfunction "28_28") (pintype "bidirectional"))
    )
    (net (code "155") (name "unconnected-(U$2-Pad29)") (class "Default")
      (node (ref "U$2") (pin "29") (pinfunction "29_29") (pintype "bidirectional"))
    )
    (net (code "156") (name "unconnected-(U$2-Pad30)") (class "Default")
      (node (ref "U$2") (pin "30") (pinfunction "30_30") (pintype "bidirectional"))
    )
    (net (code "157") (name "unconnected-(U$2-Pad31)") (class "Default")
      (node (ref "U$2") (pin "31") (pinfunction "31_31") (pintype "bidirectional"))
    )
    (net (code "158") (name "unconnected-(U$2-Pad32)") (class "Default")
      (node (ref "U$2") (pin "32") (pinfunction "32_32") (pintype "bidirectional"))
    )
    (net (code "159") (name "unconnected-(U$2-Pad33)") (class "Default")
      (node (ref "U$2") (pin "33") (pinfunction "33_33") (pintype "bidirectional"))
    )
    (net (code "160") (name "unconnected-(U$2-Pad34)") (class "Default")
      (node (ref "U$2") (pin "34") (pinfunction "34_34") (pintype "bidirectional"))
    )
    (net (code "161") (name "unconnected-(U$2-Pad35)") (class "Default")
      (node (ref "U$2") (pin "35") (pinfunction "35_35") (pintype "bidirectional"))
    )
    (net (code "162") (name "unconnected-(U$2-Pad36)") (class "Default")
      (node (ref "U$2") (pin "36") (pinfunction "36_36") (pintype "bidirectional"))
    )
    (net (code "163") (name "unconnected-(U$2-Pad37)") (class "Default")
      (node (ref "U$2") (pin "37") (pinfunction "37_37") (pintype "bidirectional"))
    )
    (net (code "164") (name "unconnected-(U$2-Pad38)") (class "Default")
      (node (ref "U$2") (pin "38") (pinfunction "38_38") (pintype "bidirectional"))
    )
    (net (code "165") (name "unconnected-(U$2-Pad39)") (class "Default")
      (node (ref "U$2") (pin "39") (pinfunction "39_39") (pintype "bidirectional"))
    )
    (net (code "166") (name "unconnected-(U$2-Pad40)") (class "Default")
      (node (ref "U$2") (pin "40") (pinfunction "40_40") (pintype "bidirectional"))
    )
    (net (code "167") (name "unconnected-(U$2-Pad41)") (class "Default")
      (node (ref "U$2") (pin "41") (pinfunction "41_41") (pintype "bidirectional"))
    )
    (net (code "168") (name "unconnected-(U$2-Pad42)") (class "Default")
      (node (ref "U$2") (pin "42") (pinfunction "42_42") (pintype "bidirectional"))
    )
    (net (code "169") (name "unconnected-(U$2-Pad43)") (class "Default")
      (node (ref "U$2") (pin "43") (pinfunction "43_43") (pintype "bidirectional"))
    )
    (net (code "170") (name "unconnected-(U$2-Pad44)") (class "Default")
      (node (ref "U$2") (pin "44") (pinfunction "44_44") (pintype "bidirectional"))
    )
    (net (code "171") (name "unconnected-(U$2-Pad45)") (class "Default")
      (node (ref "U$2") (pin "45") (pinfunction "45_45") (pintype "bidirectional"))
    )
    (net (code "172") (name "unconnected-(U$2-Pad46)") (class "Default")
      (node (ref "U$2") (pin "46") (pinfunction "46_46") (pintype "bidirectional"))
    )
    (net (code "173") (name "unconnected-(U$2-Pad47)") (class "Default")
      (node (ref "U$2") (pin "47") (pinfunction "47_47") (pintype "bidirectional"))
    )
    (net (code "174") (name "unconnected-(U$2-Pad48)") (class "Default")
      (node (ref "U$2") (pin "48") (pinfunction "48_48") (pintype "bidirectional"))
    )
    (net (code "175") (name "unconnected-(U$2-Pad49)") (class "Default")
      (node (ref "U$2") (pin "49") (pinfunction "49_49") (pintype "bidirectional"))
    )
    (net (code "176") (name "unconnected-(U$2-Pad50)") (class "Default")
      (node (ref "U$2") (pin "50") (pinfunction "50_50") (pintype "bidirectional"))
    )
    (net (code "177") (name "unconnected-(U$2-Pad51)") (class "Default")
      (node (ref "U$2") (pin "51") (pinfunction "51_51") (pintype "bidirectional"))
    )
    (net (code "178") (name "unconnected-(U$2-Pad52)") (class "Default")
      (node (ref "U$2") (pin "52") (pinfunction "52_52") (pintype "bidirectional"))
    )
    (net (code "179") (name "unconnected-(U$2-Pad53)") (class "Default")
      (node (ref "U$2") (pin "53") (pinfunction "53_53") (pintype "bidirectional"))
    )
    (net (code "180") (name "unconnected-(U$2-PadA0)") (class "Default")
      (node (ref "U$2") (pin "A0") (pinfunction "A0_A0") (pintype "bidirectional"))
    )
    (net (code "181") (name "unconnected-(U$2-PadA1)") (class "Default")
      (node (ref "U$2") (pin "A1") (pinfunction "A1_A1") (pintype "bidirectional"))
    )
    (net (code "182") (name "unconnected-(U$2-PadA2)") (class "Default")
      (node (ref "U$2") (pin "A2") (pinfunction "A2_A2") (pintype "bidirectional"))
    )
    (net (code "183") (name "unconnected-(U$2-PadA3)") (class "Default")
      (node (ref "U$2") (pin "A3") (pinfunction "A3_A3") (pintype "bidirectional"))
    )
    (net (code "184") (name "unconnected-(U$2-PadA4)") (class "Default")
      (node (ref "U$2") (pin "A4") (pinfunction "A4_A4") (pintype "bidirectional"))
    )
    (net (code "185") (name "unconnected-(U$2-PadA5)") (class "Default")
      (node (ref "U$2") (pin "A5") (pinfunction "A5_A5") (pintype "bidirectional"))
    )
    (net (code "186") (name "unconnected-(U$2-PadA6)") (class "Default")
      (node (ref "U$2") (pin "A6") (pinfunction "A6_A6") (pintype "bidirectional"))
    )
    (net (code "187") (name "unconnected-(U$2-PadA7)") (class "Default")
      (node (ref "U$2") (pin "A7") (pinfunction "A7_A7") (pintype "bidirectional"))
    )
    (net (code "188") (name "unconnected-(U$2-PadA8)") (class "Default")
      (node (ref "U$2") (pin "A8") (pinfunction "A8_A8") (pintype "bidirectional"))
    )
    (net (code "189") (name "unconnected-(U$2-PadA9)") (class "Default")
      (node (ref "U$2") (pin "A9") (pinfunction "A9_A9") (pintype "bidirectional"))
    )
    (net (code "190") (name "unconnected-(U$2-PadA10)") (class "Default")
      (node (ref "U$2") (pin "A10") (pinfunction "A10_A10") (pintype "bidirectional"))
    )
    (net (code "191") (name "unconnected-(U$2-PadA11)") (class "Default")
      (node (ref "U$2") (pin "A11") (pinfunction "A11_A11") (pintype "bidirectional"))
    )
    (net (code "192") (name "unconnected-(U$2-PadAREF)") (class "Default")
      (node (ref "U$2") (pin "AREF") (pinfunction "AREF_AREF") (pintype "bidirectional"))
    )
    (net (code "193") (name "unconnected-(U$2-PadCANRX)") (class "Default")
      (node (ref "U$2") (pin "CANRX") (pinfunction "CANRX_CANRX") (pintype "bidirectional"))
    )
    (net (code "194") (name "unconnected-(U$2-PadCANTX)") (class "Default")
      (node (ref "U$2") (pin "CANTX") (pinfunction "CANTX_CANTX") (pintype "bidirectional"))
    )
    (net (code "195") (name "unconnected-(U$2-PadDAC0)") (class "Default")
      (node (ref "U$2") (pin "DAC0") (pinfunction "DAC0_DAC0") (pintype "bidirectional"))
    )
    (net (code "196") (name "unconnected-(U$2-PadDAC1)") (class "Default")
      (node (ref "U$2") (pin "DAC1") (pinfunction "DAC1_DAC1") (pintype "bidirectional"))
    )
    (net (code "197") (name "unconnected-(U$2-PadGND1)") (class "Default")
      (node (ref "U$2") (pin "GND1") (pinfunction "GND1_GND1") (pintype "bidirectional"))
    )
    (net (code "198") (name "unconnected-(U$2-PadGND_1)") (class "Default")
      (node (ref "U$2") (pin "GND_1") (pinfunction "GND_1_GND_1") (pintype "bidirectional"))
    )
    (net (code "199") (name "unconnected-(U$2-PadGND_2)") (class "Default")
      (node (ref "U$2") (pin "GND_2") (pinfunction "GND_2_GND_2") (pintype "bidirectional"))
    )
    (net (code "200") (name "unconnected-(U$2-PadGND_A)") (class "Default")
      (node (ref "U$2") (pin "GND_A") (pinfunction "GND_A_GND_A") (pintype "bidirectional"))
    )
    (net (code "201") (name "unconnected-(U$2-PadGND_B)") (class "Default")
      (node (ref "U$2") (pin "GND_B") (pinfunction "GND_B_GND_B") (pintype "bidirectional"))
    )
    (net (code "202") (name "unconnected-(U$2-PadGND_DEBUG)") (class "Default")
      (node (ref "U$2") (pin "GND_DEBUG") (pinfunction "GND_DEBUG_GND_DEBUG") (pintype "bidirectional"))
    )
    (net (code "203") (name "unconnected-(U$2-PadGND_ICSP)") (class "Default")
      (node (ref "U$2") (pin "GND_ICSP") (pinfunction "GND_ICSP_GND_ICSP") (pintype "bidirectional"))
    )
    (net (code "204") (name "unconnected-(U$2-PadIOREF)") (class "Default")
      (node (ref "U$2") (pin "IOREF") (pinfunction "IOREF_IOREF") (pintype "bidirectional"))
    )
    (net (code "205") (name "unconnected-(U$2-PadMISO_ICSP)") (class "Default")
      (node (ref "U$2") (pin "MISO_ICSP") (pinfunction "MISO_ICSP_MISO_ICSP") (pintype "bidirectional"))
    )
    (net (code "206") (name "unconnected-(U$2-PadMOSI_ICSP)") (class "Default")
      (node (ref "U$2") (pin "MOSI_ICSP") (pinfunction "MOSI_ICSP_MOSI_ICSP") (pintype "bidirectional"))
    )
    (net (code "207") (name "unconnected-(U$2-PadNC)") (class "Default")
      (node (ref "U$2") (pin "NC") (pinfunction "NC_NC") (pintype "bidirectional"))
    )
    (net (code "208") (name "unconnected-(U$2-PadRESET)") (class "Default")
      (node (ref "U$2") (pin "RESET") (pinfunction "RESET_RESET") (pintype "bidirectional"))
    )
    (net (code "209") (name "unconnected-(U$2-PadRESET_DEBUG)") (class "Default")
      (node (ref "U$2") (pin "RESET_DEBUG") (pinfunction "RESET_DEBUG_RESET_DEBUG") (pintype "bidirectional"))
    )
    (net (code "210") (name "unconnected-(U$2-PadRESET_ICSP)") (class "Default")
      (node (ref "U$2") (pin "RESET_ICSP") (pinfunction "RESET_ICSP_RESET_ICSP") (pintype "bidirectional"))
    )
    (net (code "211") (name "unconnected-(U$2-PadRX0)") (class "Default")
      (node (ref "U$2") (pin "RX0") (pinfunction "RX0_RX0") (pintype "bidirectional"))
    )
    (net (code "212") (name "unconnected-(U$2-PadRX1)") (class "Default")
      (node (ref "U$2") (pin "RX1") (pinfunction "RX1_RX1") (pintype "bidirectional"))
    )
    (net (code "213") (name "unconnected-(U$2-PadRX2)") (class "Default")
      (node (ref "U$2") (pin "RX2") (pinfunction "RX2_RX2") (pintype "bidirectional"))
    )
    (net (code "214") (name "unconnected-(U$2-PadRX3)") (class "Default")
      (node (ref "U$2") (pin "RX3") (pinfunction "RX3_RX3") (pintype "bidirectional"))
    )
    (net (code "215") (name "unconnected-(U$2-PadSCK_ICSP)") (class "Default")
      (node (ref "U$2") (pin "SCK_ICSP") (pinfunction "SCK_ICSP_SCK_ICSP") (pintype "bidirectional"))
    )
    (net (code "216") (name "unconnected-(U$2-PadSCL)") (class "Default")
      (node (ref "U$2") (pin "SCL") (pinfunction "SCL_SCL") (pintype "bidirectional"))
    )
    (net (code "217") (name "unconnected-(U$2-PadSCL1)") (class "Default")
      (node (ref "U$2") (pin "SCL1") (pinfunction "SCL1_SCL1") (pintype "bidirectional"))
    )
    (net (code "218") (name "unconnected-(U$2-PadSDA)") (class "Default")
      (node (ref "U$2") (pin "SDA") (pinfunction "SDA_SDA") (pintype "bidirectional"))
    )
    (net (code "219") (name "unconnected-(U$2-PadSDA1)") (class "Default")
      (node (ref "U$2") (pin "SDA1") (pinfunction "SDA1_SDA1") (pintype "bidirectional"))
    )
    (net (code "220") (name "unconnected-(U$2-PadSWCLK_DEBUG)") (class "Default")
      (node (ref "U$2") (pin "SWCLK_DEBUG") (pinfunction "SWCLK_DEBUG_SWCLK_DEBUG") (pintype "bidirectional"))
    )
    (net (code "221") (name "unconnected-(U$2-PadSWDIO_DEBUG)") (class "Default")
      (node (ref "U$2") (pin "SWDIO_DEBUG") (pinfunction "SWDIO_DEBUG_SWDIO_DEBUG") (pintype "bidirectional"))
    )
    (net (code "222") (name "unconnected-(U$2-PadTX0)") (class "Default")
      (node (ref "U$2") (pin "TX0") (pinfunction "TX0_TX0") (pintype "bidirectional"))
    )
    (net (code "223") (name "unconnected-(U$2-PadTX1)") (class "Default")
      (node (ref "U$2") (pin "TX1") (pinfunction "TX1_TX1") (pintype "bidirectional"))
    )
    (net (code "224") (name "unconnected-(U$2-PadTX2)") (class "Default")
      (node (ref "U$2") (pin "TX2") (pinfunction "TX2_TX2") (pintype "bidirectional"))
    )
    (net (code "225") (name "unconnected-(U$2-PadTX3)") (class "Default")
      (node (ref "U$2") (pin "TX3") (pinfunction "TX3_TX3") (pintype "bidirectional"))
    )
    (net (code "226") (name "unconnected-(U$2-PadVIN)") (class "Default")
      (node (ref "U$2") (pin "VIN") (pinfunction "VIN_VIN") (pintype "bidirectional"))
    )
  )
)
